# h_bridge.net
KiCad netlist of a schematic drawn in EAGLE
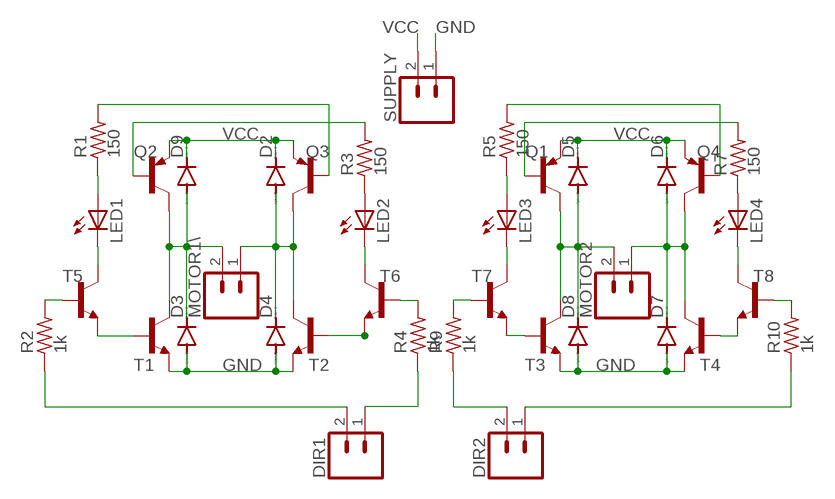
[diagram p0: schematic, sheet 1]

(export (version "E")
  (design (tool "Eeschema 10.0.6"))
  (components
    (comp (ref "D2")
      (value "DIODE-D-2.5")
      (footprint "eagle-import:D-2.5")
      (libsource (lib "eagle-import") (part "DIODE-D-2.5"))
    )
    (comp (ref "D3")
      (value "DIODE-D-2.5")
      (footprint "eagle-import:D-2.5")
      (libsource (lib "eagle-import") (part "DIODE-D-2.5"))
    )
    (comp (ref "D4")
      (value "DIODE-D-2.5")
      (footprint "eagle-import:D-2.5")
      (libsource (lib "eagle-import") (part "DIODE-D-2.5"))
    )
    (comp (ref "D5")
      (value "DIODE-D-2.5")
      (footprint "eagle-import:D-2.5")
      (libsource (lib "eagle-import") (part "DIODE-D-2.5"))
    )
    (comp (ref "D6")
      (value "DIODE-D-2.5")
      (footprint "eagle-import:D-2.5")
      (libsource (lib "eagle-import") (part "DIODE-D-2.5"))
    )
    (comp (ref "D7")
      (value "DIODE-D-2.5")
      (footprint "eagle-import:D-2.5")
      (libsource (lib "eagle-import") (part "DIODE-D-2.5"))
    )
    (comp (ref "D8")
      (value "DIODE-D-2.5")
      (footprint "eagle-import:D-2.5")
      (libsource (lib "eagle-import") (part "DIODE-D-2.5"))
    )
    (comp (ref "D9")
      (value "DIODE-D-2.5")
      (footprint "eagle-import:D-2.5")
      (libsource (lib "eagle-import") (part "DIODE-D-2.5"))
    )
    (comp (ref "DIR1")
      (value "CONN_02")
      (footprint "eagle-import:1X02")
      (libsource (lib "eagle-import") (part "CONN_02"))
    )
    (comp (ref "DIR2")
      (value "CONN_02")
      (footprint "eagle-import:1X02")
      (libsource (lib "eagle-import") (part "CONN_02"))
    )
    (comp (ref "LED1")
      (value "LED3MM")
      (footprint "eagle-import:LED3MM")
      (libsource (lib "eagle-import") (part "LED3MM"))
    )
    (comp (ref "LED2")
      (value "LED3MM")
      (footprint "eagle-import:LED3MM")
      (libsource (lib "eagle-import") (part "LED3MM"))
    )
    (comp (ref "LED3")
      (value "LED3MM")
      (footprint "eagle-import:LED3MM")
      (libsource (lib "eagle-import") (part "LED3MM"))
    )
    (comp (ref "LED4")
      (value "LED3MM")
      (footprint "eagle-import:LED3MM")
      (libsource (lib "eagle-import") (part "LED3MM"))
    )
    (comp (ref "MOTOR1\\")
      (value "CONN_02")
      (footprint "eagle-import:1X02")
      (libsource (lib "eagle-import") (part "CONN_02"))
    )
    (comp (ref "MOTOR2")
      (value "CONN_02")
      (footprint "eagle-import:1X02")
      (libsource (lib "eagle-import") (part "CONN_02"))
    )
    (comp (ref "Q1")
      (value "2N2907")
      (footprint "eagle-import:TO92-EBC-OVAL")
      (libsource (lib "eagle-import") (part "2N2907"))
    )
    (comp (ref "Q2")
      (value "2N2907")
      (footprint "eagle-import:TO92-EBC-OVAL")
      (libsource (lib "eagle-import") (part "2N2907"))
    )
    (comp (ref "Q3")
      (value "2N2907")
      (footprint "eagle-import:TO92-EBC-OVAL")
      (libsource (lib "eagle-import") (part "2N2907"))
    )
    (comp (ref "Q4")
      (value "2N2907")
      (footprint "eagle-import:TO92-EBC-OVAL")
      (libsource (lib "eagle-import") (part "2N2907"))
    )
    (comp (ref "R1")
      (value "150")
      (footprint "eagle-import:0204_7")
      (libsource (lib "eagle-import") (part "R-US_0204/7"))
    )
    (comp (ref "R2")
      (value "1k")
      (footprint "eagle-import:0204_7")
      (libsource (lib "eagle-import") (part "R-US_0204/7"))
    )
    (comp (ref "R3")
      (value "150")
      (footprint "eagle-import:0204_7")
      (libsource (lib "eagle-import") (part "R-US_0204/7"))
    )
    (comp (ref "R4")
      (value "1k")
      (footprint "eagle-import:0204_7")
      (libsource (lib "eagle-import") (part "R-US_0204/7"))
    )
    (comp (ref "R5")
      (value "150")
      (footprint "eagle-import:0204_7")
      (libsource (lib "eagle-import") (part "R-US_0204/7"))
    )
    (comp (ref "R7")
      (value "150")
      (footprint "eagle-import:0204_7")
      (libsource (lib "eagle-import") (part "R-US_0204/7"))
    )
    (comp (ref "R9")
      (value "1k")
      (footprint "eagle-import:0204_7")
      (libsource (lib "eagle-import") (part "R-US_0204/7"))
    )
    (comp (ref "R10")
      (value "1k")
      (footprint "eagle-import:0204_7")
      (libsource (lib "eagle-import") (part "R-US_0204/7"))
    )
    (comp (ref "SUPPLY")
      (value "CONN_02")
      (footprint "eagle-import:1X02")
      (libsource (lib "eagle-import") (part "CONN_02"))
    )
    (comp (ref "T1")
      (value "2N2222")
      (footprint "eagle-import:TO92-EBC-OVAL")
      (libsource (lib "eagle-import") (part "2N2222"))
    )
    (comp (ref "T2")
      (value "2N2222")
      (footprint "eagle-import:TO92-EBC-OVAL")
      (libsource (lib "eagle-import") (part "2N2222"))
    )
    (comp (ref "T3")
      (value "2N2222")
      (footprint "eagle-import:TO92-EBC-OVAL")
      (libsource (lib "eagle-import") (part "2N2222"))
    )
    (comp (ref "T4")
      (value "2N2222")
      (footprint "eagle-import:TO92-EBC-OVAL")
      (libsource (lib "eagle-import") (part "2N2222"))
    )
    (comp (ref "T5")
      (value "2N2222")
      (footprint "eagle-import:TO92-EBC-OVAL")
      (libsource (lib "eagle-import") (part "2N2222"))
    )
    (comp (ref "T6")
      (value "2N2222")
      (footprint "eagle-import:TO92-EBC-OVAL")
      (libsource (lib "eagle-import") (part "2N2222"))
    )
    (comp (ref "T7")
      (value "2N2222")
      (footprint "eagle-import:TO92-EBC-OVAL")
      (libsource (lib "eagle-import") (part "2N2222"))
    )
    (comp (ref "T8")
      (value "2N2222")
      (footprint "eagle-import:TO92-EBC-OVAL")
      (libsource (lib "eagle-import") (part "2N2222"))
    )
  )
  (nets
    (net (code "1") (name "/GND") (class "Default")
      (node (ref "D3") (pin "A") (pinfunction "A_A") (pintype "passive"))
      (node (ref "D4") (pin "A") (pinfunction "A_A") (pintype "passive"))
      (node (ref "D7") (pin "A") (pinfunction "A_A") (pintype "passive"))
      (node (ref "D8") (pin "A") (pinfunction "A_A") (pintype "passive"))
      (node (ref "SUPPLY") (pin "1") (pinfunction "1_1") (pintype "passive"))
      (node (ref "T1") (pin "E") (pinfunction "E_E") (pintype "passive"))
      (node (ref "T2") (pin "E") (pinfunction "E_E") (pintype "passive"))
      (node (ref "T3") (pin "E") (pinfunction "E_E") (pintype "passive"))
      (node (ref "T4") (pin "E") (pinfunction "E_E") (pintype "passive"))
    )
    (net (code "2") (name "/VCC") (class "Default")
      (node (ref "D2") (pin "C") (pinfunction "C_C") (pintype "passive"))
      (node (ref "D5") (pin "C") (pinfunction "C_C") (pintype "passive"))
      (node (ref "D6") (pin "C") (pinfunction "C_C") (pintype "passive"))
      (node (ref "D9") (pin "C") (pinfunction "C_C") (pintype "passive"))
      (node (ref "Q1") (pin "E") (pinfunction "E_E") (pintype "passive"))
      (node (ref "Q2") (pin "E") (pinfunction "E_E") (pintype "passive"))
      (node (ref "Q3") (pin "E") (pinfunction "E_E") (pintype "passive"))
      (node (ref "Q4") (pin "E") (pinfunction "E_E") (pintype "passive"))
      (node (ref "SUPPLY") (pin "2") (pinfunction "2_2") (pintype "passive"))
    )
    (net (code "3") (name "Net-(D2-PadA)") (class "Default")
      (node (ref "D2") (pin "A") (pinfunction "A_A") (pintype "passive"))
      (node (ref "D4") (pin "C") (pinfunction "C_C") (pintype "passive"))
      (node (ref "MOTOR1\\") (pin "1") (pinfunction "1_1") (pintype "passive"))
      (node (ref "Q3") (pin "C") (pinfunction "C_C") (pintype "passive"))
      (node (ref "T2") (pin "C") (pinfunction "C_C") (pintype "passive"))
    )
    (net (code "4") (name "Net-(D3-PadC)") (class "Default")
      (node (ref "D3") (pin "C") (pinfunction "C_C") (pintype "passive"))
      (node (ref "D9") (pin "A") (pinfunction "A_A") (pintype "passive"))
      (node (ref "MOTOR1\\") (pin "2") (pinfunction "2_2") (pintype "passive"))
      (node (ref "Q2") (pin "C") (pinfunction "C_C") (pintype "passive"))
      (node (ref "T1") (pin "C") (pinfunction "C_C") (pintype "passive"))
    )
    (net (code "5") (name "Net-(D5-PadA)") (class "Default")
      (node (ref "D5") (pin "A") (pinfunction "A_A") (pintype "passive"))
      (node (ref "D8") (pin "C") (pinfunction "C_C") (pintype "passive"))
      (node (ref "MOTOR2") (pin "2") (pinfunction "2_2") (pintype "passive"))
      (node (ref "Q1") (pin "C") (pinfunction "C_C") (pintype "passive"))
      (node (ref "T3") (pin "C") (pinfunction "C_C") (pintype "passive"))
    )
    (net (code "6") (name "Net-(D6-PadA)") (class "Default")
      (node (ref "D6") (pin "A") (pinfunction "A_A") (pintype "passive"))
      (node (ref "D7") (pin "C") (pinfunction "C_C") (pintype "passive"))
      (node (ref "MOTOR2") (pin "1") (pinfunction "1_1") (pintype "passive"))
      (node (ref "Q4") (pin "C") (pinfunction "C_C") (pintype "passive"))
      (node (ref "T4") (pin "C") (pinfunction "C_C") (pintype "passive"))
    )
    (net (code "7") (name "Net-(DIR1-Pad1)") (class "Default")
      (node (ref "DIR1") (pin "1") (pinfunction "1_1") (pintype "passive"))
      (node (ref "R4") (pin "1") (pinfunction "1_1") (pintype "passive"))
    )
    (net (code "8") (name "Net-(DIR1-Pad2)") (class "Default")
      (node (ref "DIR1") (pin "2") (pinfunction "2_2") (pintype "passive"))
      (node (ref "R2") (pin "1") (pinfunction "1_1") (pintype "passive"))
    )
    (net (code "9") (name "Net-(DIR2-Pad1)") (class "Default")
      (node (ref "DIR2") (pin "1") (pinfunction "1_1") (pintype "passive"))
      (node (ref "R10") (pin "1") (pinfunction "1_1") (pintype "passive"))
    )
    (net (code "10") (name "Net-(DIR2-Pad2)") (class "Default")
      (node (ref "DIR2") (pin "2") (pinfunction "2_2") (pintype "passive"))
      (node (ref "R9") (pin "1") (pinfunction "1_1") (pintype "passive"))
    )
    (net (code "11") (name "Net-(LED1-C)") (class "Default")
      (node (ref "LED1") (pin "K") (pinfunction "C_K") (pintype "passive"))
      (node (ref "T5") (pin "C") (pinfunction "C_C") (pintype "passive"))
    )
    (net (code "12") (name "Net-(LED1-PadA)") (class "Default")
      (node (ref "LED1") (pin "A") (pinfunction "A_A") (pintype "passive"))
      (node (ref "R1") (pin "1") (pinfunction "1_1") (pintype "passive"))
    )
    (net (code "13") (name "Net-(LED2-C)") (class "Default")
      (node (ref "LED2") (pin "K") (pinfunction "C_K") (pintype "passive"))
      (node (ref "T6") (pin "C") (pinfunction "C_C") (pintype "passive"))
    )
    (net (code "14") (name "Net-(LED2-PadA)") (class "Default")
      (node (ref "LED2") (pin "A") (pinfunction "A_A") (pintype "passive"))
      (node (ref "R3") (pin "1") (pinfunction "1_1") (pintype "passive"))
    )
    (net (code "15") (name "Net-(LED3-C)") (class "Default")
      (node (ref "LED3") (pin "K") (pinfunction "C_K") (pintype "passive"))
      (node (ref "T7") (pin "C") (pinfunction "C_C") (pintype "passive"))
    )
    (net (code "16") (name "Net-(LED3-PadA)") (class "Default")
      (node (ref "LED3") (pin "A") (pinfunction "A_A") (pintype "passive"))
      (node (ref "R5") (pin "1") (pinfunction "1_1") (pintype "passive"))
    )
    (net (code "17") (name "Net-(LED4-C)") (class "Default")
      (node (ref "LED4") (pin "K") (pinfunction "C_K") (pintype "passive"))
      (node (ref "T8") (pin "C") (pinfunction "C_C") (pintype "passive"))
    )
    (net (code "18") (name "Net-(LED4-PadA)") (class "Default")
      (node (ref "LED4") (pin "A") (pinfunction "A_A") (pintype "passive"))
      (node (ref "R7") (pin "1") (pinfunction "1_1") (pintype "passive"))
    )
    (net (code "19") (name "Net-(Q1-PadB)") (class "Default")
      (node (ref "Q1") (pin "B") (pinfunction "B_B") (pintype "passive"))
      (node (ref "R7") (pin "2") (pinfunction "2_2") (pintype "passive"))
    )
    (net (code "20") (name "Net-(Q2-PadB)") (class "Default")
      (node (ref "Q2") (pin "B") (pinfunction "B_B") (pintype "passive"))
      (node (ref "R3") (pin "2") (pinfunction "2_2") (pintype "passive"))
    )
    (net (code "21") (name "Net-(Q3-PadB)") (class "Default")
      (node (ref "Q3") (pin "B") (pinfunction "B_B") (pintype "passive"))
      (node (ref "R1") (pin "2") (pinfunction "2_2") (pintype "passive"))
    )
    (net (code "22") (name "Net-(Q4-PadB)") (class "Default")
      (node (ref "Q4") (pin "B") (pinfunction "B_B") (pintype "passive"))
      (node (ref "R5") (pin "2") (pinfunction "2_2") (pintype "passive"))
    )
    (net (code "23") (name "Net-(R2-Pad2)") (class "Default")
      (node (ref "R2") (pin "2") (pinfunction "2_2") (pintype "passive"))
      (node (ref "T5") (pin "B") (pinfunction "B_B") (pintype "passive"))
    )
    (net (code "24") (name "Net-(R4-Pad2)") (class "Default")
      (node (ref "R4") (pin "2") (pinfunction "2_2") (pintype "passive"))
      (node (ref "T6") (pin "B") (pinfunction "B_B") (pintype "passive"))
    )
    (net (code "25") (name "Net-(R9-Pad2)") (class "Default")
      (node (ref "R9") (pin "2") (pinfunction "2_2") (pintype "passive"))
      (node (ref "T7") (pin "B") (pinfunction "B_B") (pintype "passive"))
    )
    (net (code "26") (name "Net-(R10-Pad2)") (class "Default")
      (node (ref "R10") (pin "2") (pinfunction "2_2") (pintype "passive"))
      (node (ref "T8") (pin "B") (pinfunction "B_B") (pintype "passive"))
    )
    (net (code "27") (name "Net-(T1-PadB)") (class "Default")
      (node (ref "T1") (pin "B") (pinfunction "B_B") (pintype "passive"))
      (node (ref "T5") (pin "E") (pinfunction "E_E") (pintype "passive"))
    )
    (net (code "28") (name "Net-(T2-PadB)") (class "Default")
      (node (ref "T2") (pin "B") (pinfunction "B_B") (pintype "passive"))
      (node (ref "T6") (pin "E") (pinfunction "E_E") (pintype "passive"))
    )
    (net (code "29") (name "Net-(T3-PadB)") (class "Default")
      (node (ref "T3") (pin "B") (pinfunction "B_B") (pintype "passive"))
      (node (ref "T7") (pin "E") (pinfunction "E_E") (pintype "passive"))
    )
    (net (code "30") (name "Net-(T4-PadB)") (class "Default")
      (node (ref "T4") (pin "B") (pinfunction "B_B") (pintype "passive"))
      (node (ref "T8") (pin "E") (pinfunction "E_E") (pintype "passive"))
    )
  )
)
